# LightSensorCircuitNoAmp_BTSeriesHookup_-.net
KiCad netlist of a schematic drawn in EAGLE
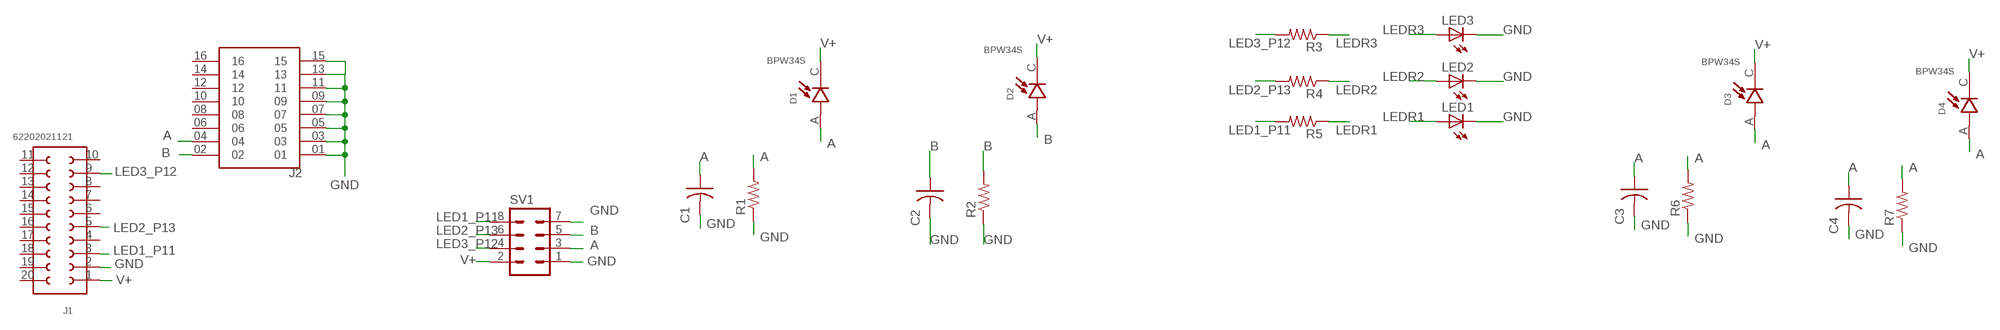
[diagram p0: schematic, sheet 1]

(export (version "E")
  (design (tool "Eeschema 10.0.6"))
  (components
    (comp (ref "C1")
      (value "C-US025-025X050")
      (footprint "eagle-import:C025-025X050")
      (libsource (lib "eagle-import") (part "C-US025-025X050"))
    )
    (comp (ref "C2")
      (value "C-US025-025X050")
      (footprint "eagle-import:C025-025X050")
      (libsource (lib "eagle-import") (part "C-US025-025X050"))
    )
    (comp (ref "C3")
      (value "C-US025-025X050")
      (footprint "eagle-import:C025-025X050")
      (libsource (lib "eagle-import") (part "C-US025-025X050"))
    )
    (comp (ref "C4")
      (value "C-US025-025X050")
      (footprint "eagle-import:C025-025X050")
      (libsource (lib "eagle-import") (part "C-US025-025X050"))
    )
    (comp (ref "D1")
      (value "BPW34S")
      (footprint "eagle-import:DIO_BPW34S")
      (fields (field (name "MF") "Vishay Semiconductor Opto Division"))
      (libsource (lib "eagle-import") (part "BPW34S"))
    )
    (comp (ref "D2")
      (value "BPW34S")
      (footprint "eagle-import:DIO_BPW34S")
      (fields (field (name "MF") "Vishay Semiconductor Opto Division"))
      (libsource (lib "eagle-import") (part "BPW34S"))
    )
    (comp (ref "D3")
      (value "BPW34S")
      (footprint "eagle-import:DIO_BPW34S")
      (fields (field (name "MF") "Vishay Semiconductor Opto Division"))
      (libsource (lib "eagle-import") (part "BPW34S"))
    )
    (comp (ref "D4")
      (value "BPW34S")
      (footprint "eagle-import:DIO_BPW34S")
      (fields (field (name "MF") "Vishay Semiconductor Opto Division"))
      (libsource (lib "eagle-import") (part "BPW34S"))
    )
    (comp (ref "J1")
      (value "62202021121")
      (footprint "eagle-import:62202021121")
      (fields (field (name "MF") "Würth Elektronik"))
      (libsource (lib "eagle-import") (part "62202021121"))
    )
    (comp (ref "J2")
      (value "FTSH-108-02-LM-D-ES")
      (footprint "eagle-import:SAMTEC_FTSH-108-02-LM-D-ES")
      (fields (field (name "MF") "Samtec"))
      (libsource (lib "eagle-import") (part "FTSH-108-02-LM-D-ES"))
    )
    (comp (ref "LED1")
      (value "LEDCHIPLED_1206")
      (footprint "eagle-import:CHIPLED_1206")
      (libsource (lib "eagle-import") (part "LEDCHIPLED_1206"))
    )
    (comp (ref "LED2")
      (value "LEDCHIPLED_1206")
      (footprint "eagle-import:CHIPLED_1206")
      (libsource (lib "eagle-import") (part "LEDCHIPLED_1206"))
    )
    (comp (ref "LED3")
      (value "LEDCHIPLED_1206")
      (footprint "eagle-import:CHIPLED_1206")
      (libsource (lib "eagle-import") (part "LEDCHIPLED_1206"))
    )
    (comp (ref "R1")
      (value "R-US_0204/5")
      (footprint "eagle-import:0204_5")
      (libsource (lib "eagle-import") (part "R-US_0204/5"))
    )
    (comp (ref "R2")
      (value "R-US_0204/5")
      (footprint "eagle-import:0204_5")
      (libsource (lib "eagle-import") (part "R-US_0204/5"))
    )
    (comp (ref "R3")
      (value "R-US_0204/5")
      (footprint "eagle-import:0204_5")
      (libsource (lib "eagle-import") (part "R-US_0204/5"))
    )
    (comp (ref "R4")
      (value "R-US_0204/5")
      (footprint "eagle-import:0204_5")
      (libsource (lib "eagle-import") (part "R-US_0204/5"))
    )
    (comp (ref "R5")
      (value "R-US_0204/5")
      (footprint "eagle-import:0204_5")
      (libsource (lib "eagle-import") (part "R-US_0204/5"))
    )
    (comp (ref "R6")
      (value "R-US_0204/5")
      (footprint "eagle-import:0204_5")
      (libsource (lib "eagle-import") (part "R-US_0204/5"))
    )
    (comp (ref "R7")
      (value "R-US_0204/5")
      (footprint "eagle-import:0204_5")
      (libsource (lib "eagle-import") (part "R-US_0204/5"))
    )
    (comp (ref "SV1")
      (value "MA04-2")
      (footprint "eagle-import:MA04-2")
      (libsource (lib "eagle-import") (part "MA04-2"))
    )
  )
  (nets
    (net (code "1") (name "/A") (class "Default")
      (node (ref "C1") (pin "1") (pinfunction "1_1") (pintype "passive"))
      (node (ref "C3") (pin "1") (pinfunction "1_1") (pintype "passive"))
      (node (ref "C4") (pin "1") (pinfunction "1_1") (pintype "passive"))
      (node (ref "D1") (pin "A") (pinfunction "A_A") (pintype "passive"))
      (node (ref "D3") (pin "A") (pinfunction "A_A") (pintype "passive"))
      (node (ref "D4") (pin "A") (pinfunction "A_A") (pintype "passive"))
      (node (ref "J2") (pin "04") (pinfunction "04_04") (pintype "passive"))
      (node (ref "R1") (pin "2") (pinfunction "2_2") (pintype "passive"))
      (node (ref "R6") (pin "2") (pinfunction "2_2") (pintype "passive"))
      (node (ref "R7") (pin "2") (pinfunction "2_2") (pintype "passive"))
      (node (ref "SV1") (pin "3") (pinfunction "3_3") (pintype "passive"))
    )
    (net (code "2") (name "/B") (class "Default")
      (node (ref "C2") (pin "1") (pinfunction "1_1") (pintype "passive"))
      (node (ref "D2") (pin "A") (pinfunction "A_A") (pintype "passive"))
      (node (ref "J2") (pin "02") (pinfunction "02_02") (pintype "passive"))
      (node (ref "R2") (pin "2") (pinfunction "2_2") (pintype "passive"))
      (node (ref "SV1") (pin "5") (pinfunction "5_5") (pintype "passive"))
    )
    (net (code "3") (name "/GND") (class "Default")
      (node (ref "C1") (pin "2") (pinfunction "2_2") (pintype "passive"))
      (node (ref "C2") (pin "2") (pinfunction "2_2") (pintype "passive"))
      (node (ref "C3") (pin "2") (pinfunction "2_2") (pintype "passive"))
      (node (ref "C4") (pin "2") (pinfunction "2_2") (pintype "passive"))
      (node (ref "J1") (pin "2") (pinfunction "2_2") (pintype "passive"))
      (node (ref "J2") (pin "01") (pinfunction "01_01") (pintype "passive"))
      (node (ref "J2") (pin "03") (pinfunction "03_03") (pintype "passive"))
      (node (ref "J2") (pin "05") (pinfunction "05_05") (pintype "passive"))
      (node (ref "J2") (pin "07") (pinfunction "07_07") (pintype "passive"))
      (node (ref "J2") (pin "09") (pinfunction "09_09") (pintype "passive"))
      (node (ref "J2") (pin "11") (pinfunction "11_11") (pintype "passive"))
      (node (ref "J2") (pin "13") (pinfunction "13_13") (pintype "passive"))
      (node (ref "J2") (pin "15") (pinfunction "15_15") (pintype "passive"))
      (node (ref "LED1") (pin "C") (pinfunction "C_C") (pintype "passive"))
      (node (ref "LED2") (pin "C") (pinfunction "C_C") (pintype "passive"))
      (node (ref "LED3") (pin "C") (pinfunction "C_C") (pintype "passive"))
      (node (ref "R1") (pin "1") (pinfunction "1_1") (pintype "passive"))
      (node (ref "R2") (pin "1") (pinfunction "1_1") (pintype "passive"))
      (node (ref "R6") (pin "1") (pinfunction "1_1") (pintype "passive"))
      (node (ref "R7") (pin "1") (pinfunction "1_1") (pintype "passive"))
      (node (ref "SV1") (pin "1") (pinfunction "1_1") (pintype "passive"))
      (node (ref "SV1") (pin "7") (pinfunction "7_7") (pintype "passive"))
    )
    (net (code "4") (name "/LED1_P11") (class "Default")
      (node (ref "J1") (pin "3") (pinfunction "3_3") (pintype "passive"))
      (node (ref "R5") (pin "2") (pinfunction "2_2") (pintype "passive"))
      (node (ref "SV1") (pin "8") (pinfunction "8_8") (pintype "passive"))
    )
    (net (code "5") (name "/LED2_P13") (class "Default")
      (node (ref "J1") (pin "5") (pinfunction "5_5") (pintype "passive"))
      (node (ref "R4") (pin "2") (pinfunction "2_2") (pintype "passive"))
      (node (ref "SV1") (pin "6") (pinfunction "6_6") (pintype "passive"))
    )
    (net (code "6") (name "/LED3_P12") (class "Default")
      (node (ref "J1") (pin "9") (pinfunction "9_9") (pintype "passive"))
      (node (ref "R3") (pin "2") (pinfunction "2_2") (pintype "passive"))
      (node (ref "SV1") (pin "4") (pinfunction "4_4") (pintype "passive"))
    )
    (net (code "7") (name "/LEDR1") (class "Default")
      (node (ref "LED1") (pin "A") (pinfunction "A_A") (pintype "passive"))
      (node (ref "R5") (pin "1") (pinfunction "1_1") (pintype "passive"))
    )
    (net (code "8") (name "/LEDR2") (class "Default")
      (node (ref "LED2") (pin "A") (pinfunction "A_A") (pintype "passive"))
      (node (ref "R4") (pin "1") (pinfunction "1_1") (pintype "passive"))
    )
    (net (code "9") (name "/LEDR3") (class "Default")
      (node (ref "LED3") (pin "A") (pinfunction "A_A") (pintype "passive"))
      (node (ref "R3") (pin "1") (pinfunction "1_1") (pintype "passive"))
    )
    (net (code "10") (name "/V+") (class "Default")
      (node (ref "D1") (pin "C") (pinfunction "C_C") (pintype "passive"))
      (node (ref "D2") (pin "C") (pinfunction "C_C") (pintype "passive"))
      (node (ref "D3") (pin "C") (pinfunction "C_C") (pintype "passive"))
      (node (ref "D4") (pin "C") (pinfunction "C_C") (pintype "passive"))
      (node (ref "J1") (pin "1") (pinfunction "1_1") (pintype "passive"))
      (node (ref "SV1") (pin "2") (pinfunction "2_2") (pintype "passive"))
    )
    (net (code "11") (name "unconnected-(J1-Pad4)") (class "Default")
      (node (ref "J1") (pin "4") (pinfunction "4_4") (pintype "passive"))
    )
    (net (code "12") (name "unconnected-(J1-Pad6)") (class "Default")
      (node (ref "J1") (pin "6") (pinfunction "6_6") (pintype "passive"))
    )
    (net (code "13") (name "unconnected-(J1-Pad7)") (class "Default")
      (node (ref "J1") (pin "7") (pinfunction "7_7") (pintype "passive"))
    )
    (net (code "14") (name "unconnected-(J1-Pad8)") (class "Default")
      (node (ref "J1") (pin "8") (pinfunction "8_8") (pintype "passive"))
    )
    (net (code "15") (name "unconnected-(J1-Pad10)") (class "Default")
      (node (ref "J1") (pin "10") (pinfunction "10_10") (pintype "passive"))
    )
    (net (code "16") (name "unconnected-(J1-Pad11)") (class "Default")
      (node (ref "J1") (pin "11") (pinfunction "11_11") (pintype "passive"))
    )
    (net (code "17") (name "unconnected-(J1-Pad12)") (class "Default")
      (node (ref "J1") (pin "12") (pinfunction "12_12") (pintype "passive"))
    )
    (net (code "18") (name "unconnected-(J1-Pad13)") (class "Default")
      (node (ref "J1") (pin "13") (pinfunction "13_13") (pintype "passive"))
    )
    (net (code "19") (name "unconnected-(J1-Pad14)") (class "Default")
      (node (ref "J1") (pin "14") (pinfunction "14_14") (pintype "passive"))
    )
    (net (code "20") (name "unconnected-(J1-Pad15)") (class "Default")
      (node (ref "J1") (pin "15") (pinfunction "15_15") (pintype "passive"))
    )
    (net (code "21") (name "unconnected-(J1-Pad16)") (class "Default")
      (node (ref "J1") (pin "16") (pinfunction "16_16") (pintype "passive"))
    )
    (net (code "22") (name "unconnected-(J1-Pad17)") (class "Default")
      (node (ref "J1") (pin "17") (pinfunction "17_17") (pintype "passive"))
    )
    (net (code "23") (name "unconnected-(J1-Pad18)") (class "Default")
      (node (ref "J1") (pin "18") (pinfunction "18_18") (pintype "passive"))
    )
    (net (code "24") (name "unconnected-(J1-Pad19)") (class "Default")
      (node (ref "J1") (pin "19") (pinfunction "19_19") (pintype "passive"))
    )
    (net (code "25") (name "unconnected-(J1-Pad20)") (class "Default")
      (node (ref "J1") (pin "20") (pinfunction "20_20") (pintype "passive"))
    )
    (net (code "26") (name "unconnected-(J2-Pad06)") (class "Default")
      (node (ref "J2") (pin "06") (pinfunction "06_06") (pintype "passive"))
    )
    (net (code "27") (name "unconnected-(J2-Pad08)") (class "Default")
      (node (ref "J2") (pin "08") (pinfunction "08_08") (pintype "passive"))
    )
    (net (code "28") (name "unconnected-(J2-Pad10)") (class "Default")
      (node (ref "J2") (pin "10") (pinfunction "10_10") (pintype "passive"))
    )
    (net (code "29") (name "unconnected-(J2-Pad12)") (class "Default")
      (node (ref "J2") (pin "12") (pinfunction "12_12") (pintype "passive"))
    )
    (net (code "30") (name "unconnected-(J2-Pad14)") (class "Default")
      (node (ref "J2") (pin "14") (pinfunction "14_14") (pintype "passive"))
    )
    (net (code "31") (name "unconnected-(J2-Pad16)") (class "Default")
      (node (ref "J2") (pin "16") (pinfunction "16_16") (pintype "passive"))
    )
  )
)
